# BUCK.net
KiCad netlist of a schematic drawn in Altium Designer
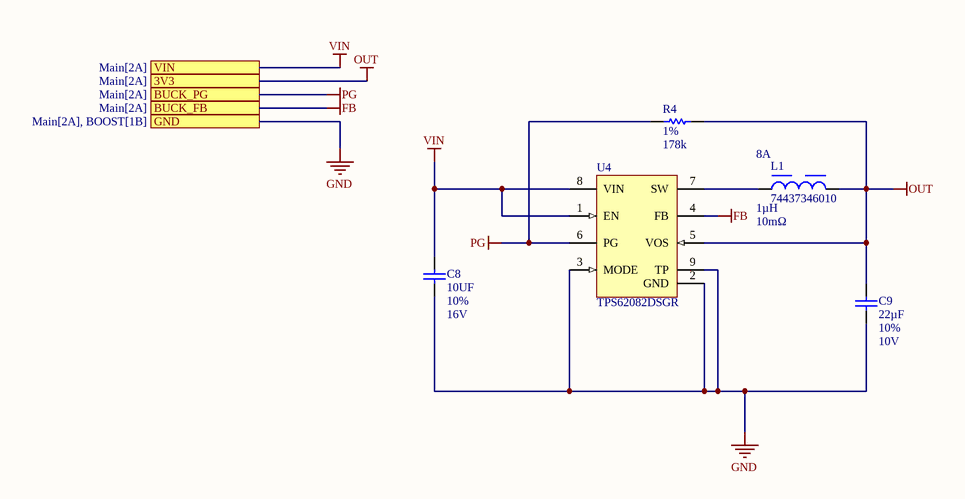
[diagram p0: BUCK.SchDoc]

(export (version "E")
  (design (tool "Eeschema 10.0.6"))
  (components
    (comp (ref "C8")
      (value "10UF")
      (footprint "1206_CAP")
      (description "Capacitor Surface Mount 1206 Footprint 10UF 16V 10% Tolerance Ceramic X7R")
      (fields
        (field (name "MANUFACTURER") "Various")
        (field (name "TOLERANCE") "10%")
        (field (name "VOLTAGE") "16V")
        (field (name "Comment") "CAP 1206 10UF 16V 10% X7R")
      )
      (libsource (lib "University of Pennsylvania (ESE)") (part "cap"))
    )
    (comp (ref "C9")
      (value "22µF")
      (footprint "1206_CAP_75H")
      (description "Capacitor Surface Mount 1206 Footprint 22UF 10V 10% Tolerance Ceramic X7R")
      (fields
        (field (name "JLCPCB PART #") "C5672")
        (field (name "TOLERANCE") "10%")
        (field (name "VOLTAGE") "10V")
        (field (name "MANUFACTURER") "Various")
      )
      (libsource (lib "University of Pennsylvania (ESE)") (part "cap"))
    )
    (comp (ref "L1")
      (value "74437346010")
      (footprint "WE-LHMI_7030")
      (fields
        (field (name "SERIES RESISTANCE") "10mΩ")
        (field (name "INDUCTANCE") "1µH")
        (field (name "CURRENT RATING") "8A")
        (field (name "TOLERANCE") "20%")
      )
      (libsource (lib "Altium Content Vault") (part "Inductor - 3"))
    )
    (comp (ref "R4")
      (value "178k")
      (footprint "0603_RES")
      (description "Resistor Surface Mount, 178K Ohms, 0603 Footprint, 1% Tolerance 0.1W")
      (fields
        (field (name "TOLERANCE") "1%")
        (field (name "MANUFACTURER") "Various")
        (field (name "Comment") "RES 0603 178K 1%")
      )
      (libsource (lib "University of Pennsylvania (ESE)") (part "res"))
    )
    (comp (ref "U4")
      (value "TPS62082DSGR")
      (footprint "DSG0008A_V")
      (fields (field (name "MANUFACTURER") "Texas Instruments"))
      (libsource (lib "Altium Content Vault") (part "TI-TPS62082DSG8-1600X900TP"))
    )
  )
  (nets
    (net (code "1") (name "FB") (class "Default")
      (node (ref "U4") (pin "4") (pinfunction "FB_4") (pintype "passive"))
    )
    (net (code "2") (name "GND") (class "Default")
      (node (ref "C8") (pin "1") (pinfunction "1_1") (pintype "passive"))
      (node (ref "C9") (pin "1") (pinfunction "1_1") (pintype "passive"))
      (node (ref "U4") (pin "2") (pinfunction "GND_2") (pintype "power_in"))
      (node (ref "U4") (pin "3") (pinfunction "MODE_3") (pintype "input"))
      (node (ref "U4") (pin "9") (pinfunction "TP_9") (pintype "power_in"))
    )
    (net (code "3") (name "Net-(U4-SW)") (class "Default")
      (node (ref "L1") (pin "1") (pinfunction "1_1") (pintype "passive"))
      (node (ref "U4") (pin "7") (pinfunction "SW_7") (pintype "power_in"))
    )
    (net (code "4") (name "OUT") (class "Default")
      (node (ref "C9") (pin "2") (pinfunction "2_2") (pintype "passive"))
      (node (ref "L1") (pin "2") (pinfunction "2_2") (pintype "passive"))
      (node (ref "R4") (pin "1") (pinfunction "1_1") (pintype "passive"))
      (node (ref "U4") (pin "5") (pinfunction "VOS_5") (pintype "input"))
    )
    (net (code "5") (name "PG") (class "Default")
      (node (ref "R4") (pin "2") (pinfunction "2_2") (pintype "passive"))
      (node (ref "U4") (pin "6") (pinfunction "PG_6") (pintype "tri_state"))
    )
    (net (code "6") (name "VIN") (class "Default")
      (node (ref "C8") (pin "2") (pinfunction "2_2") (pintype "passive"))
      (node (ref "U4") (pin "1") (pinfunction "EN_1") (pintype "input"))
      (node (ref "U4") (pin "8") (pinfunction "VIN_8") (pintype "power_in"))
    )
  )
)
